# eMMC.net
KiCad netlist of a schematic drawn in Altium Designer
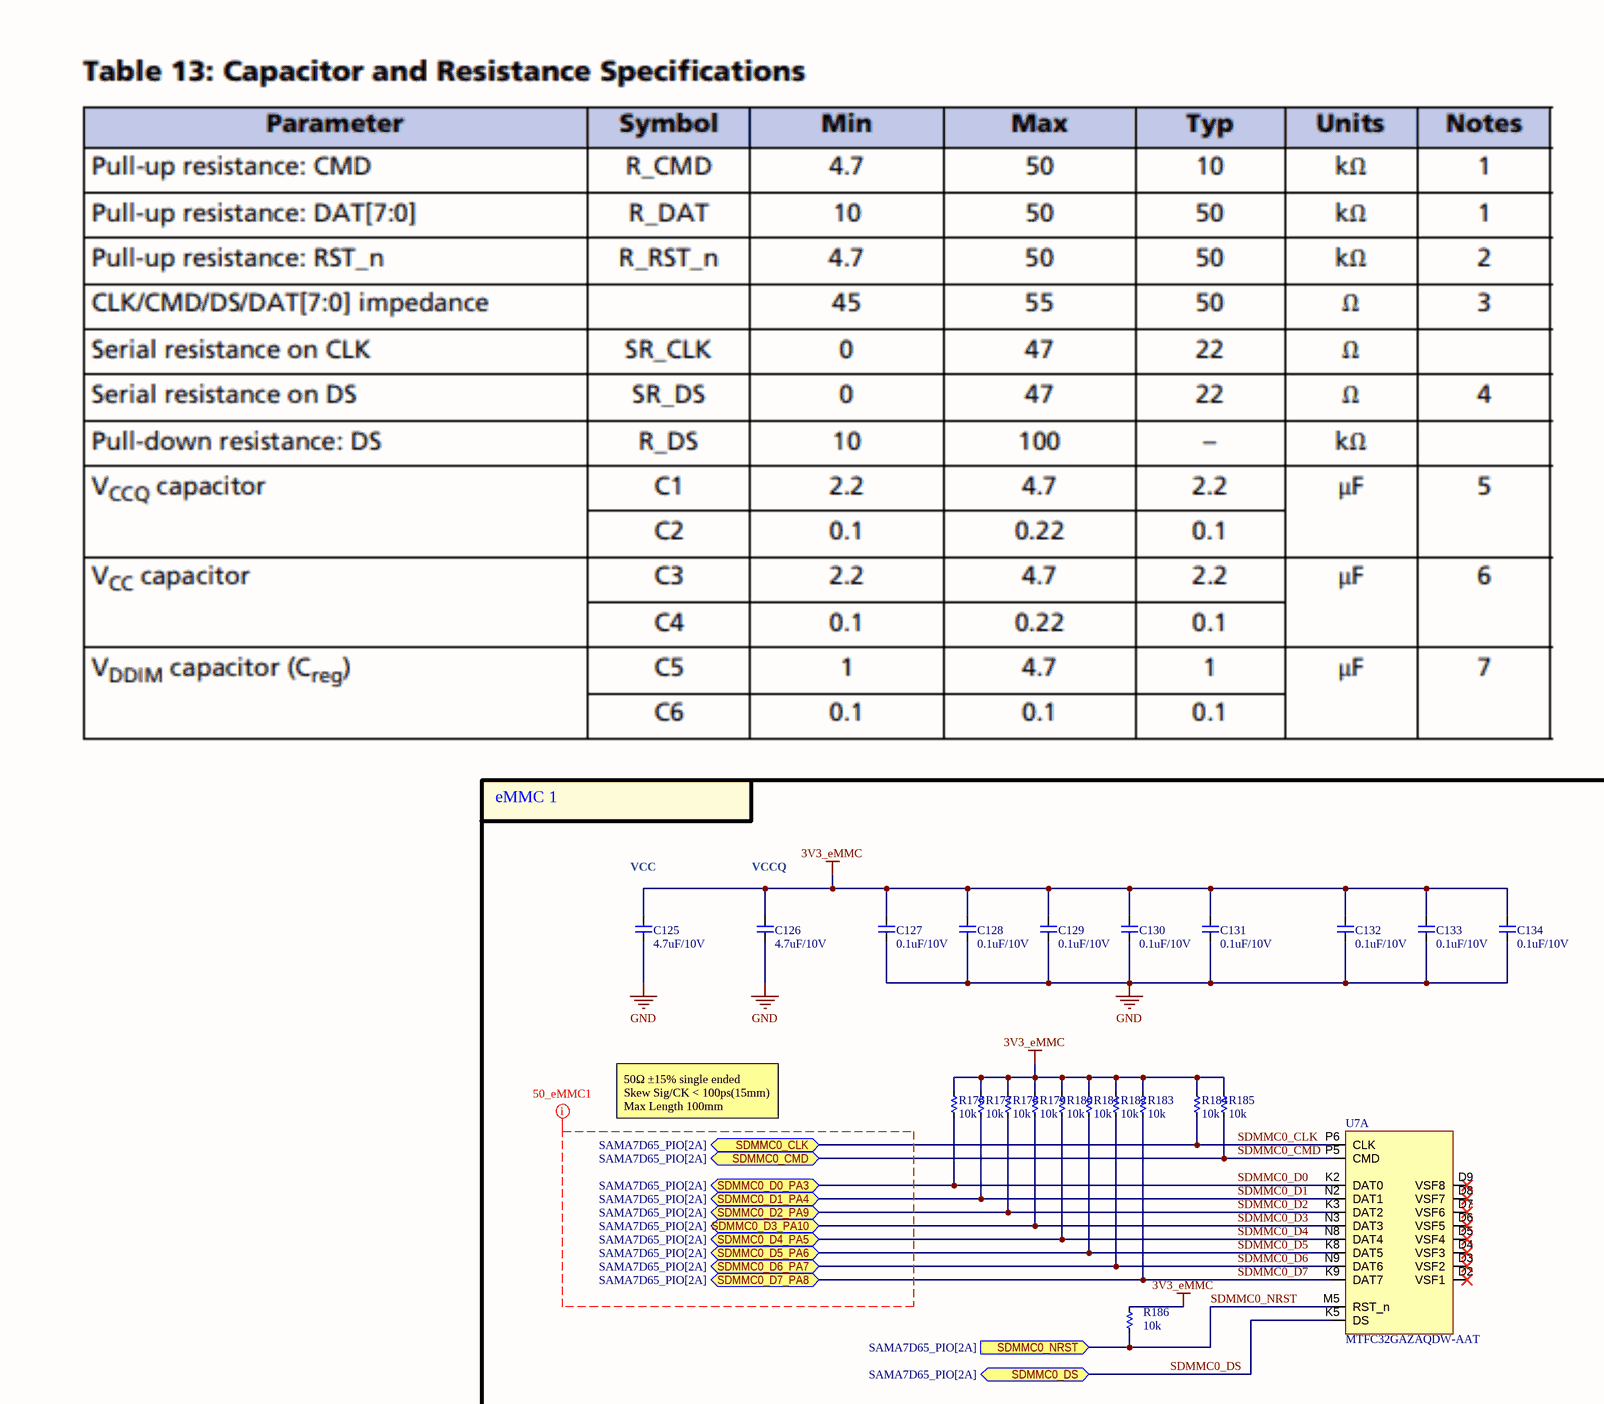
[diagram p0: eMMC.SchDoc, top left]
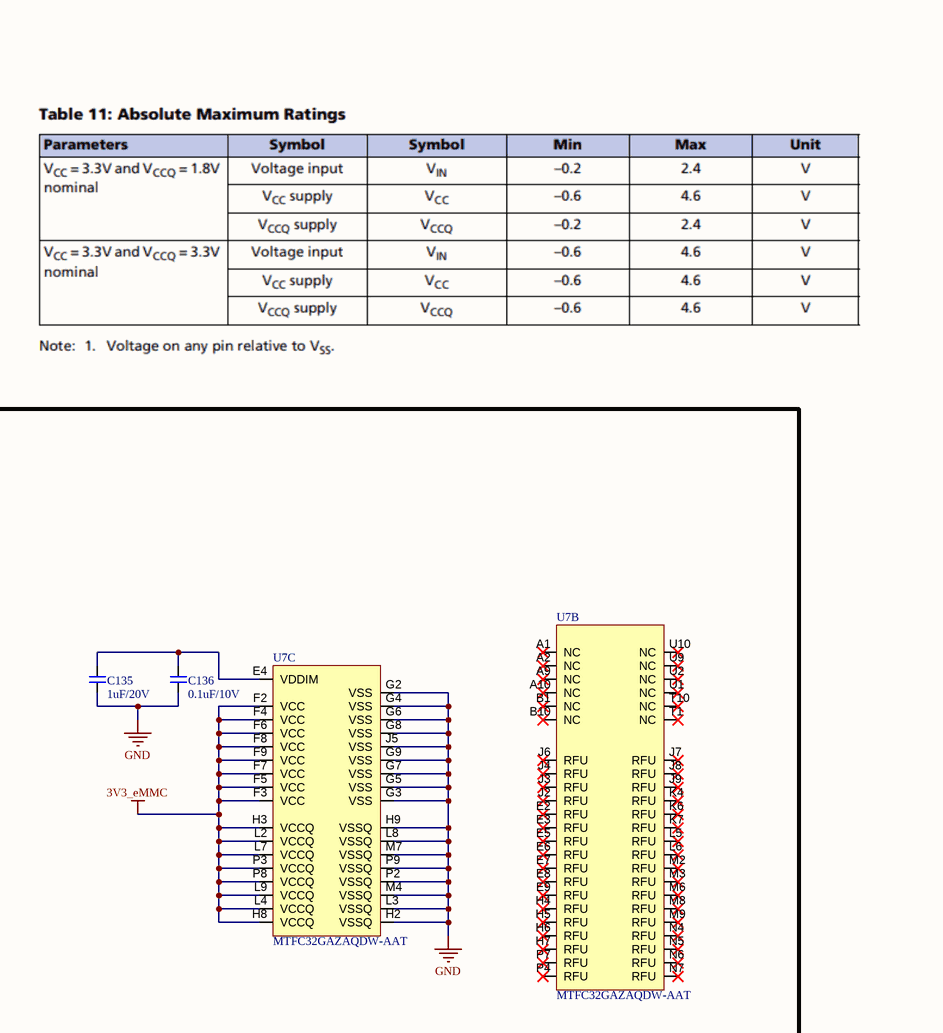
[diagram p1: eMMC.SchDoc, top middle]
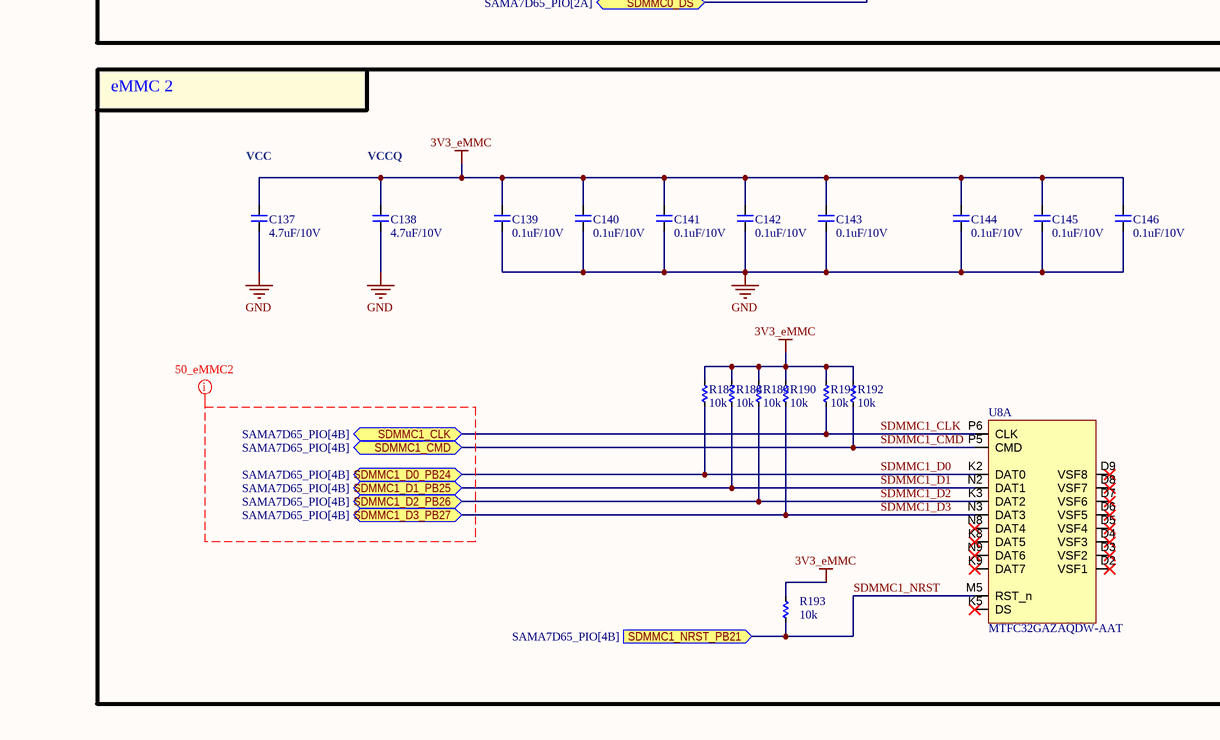
[diagram p2: eMMC.SchDoc, bottom left]
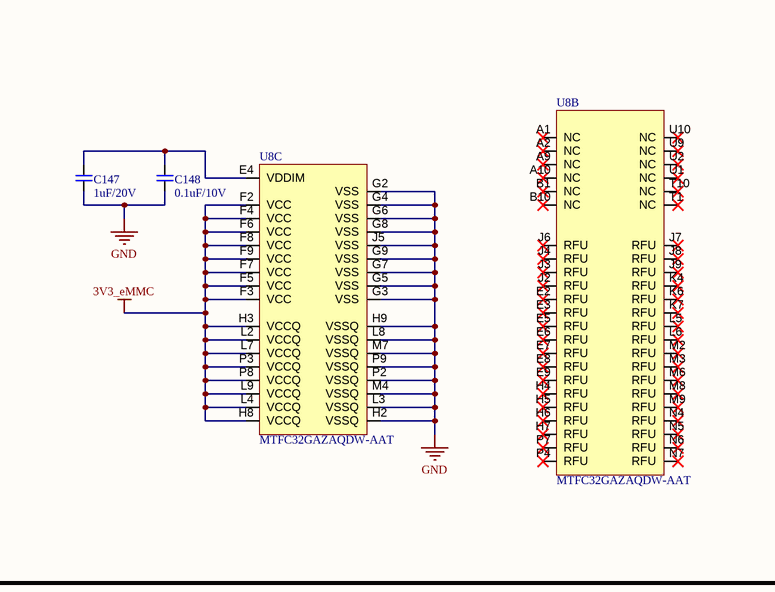
[diagram p3: eMMC.SchDoc, bottom middle]
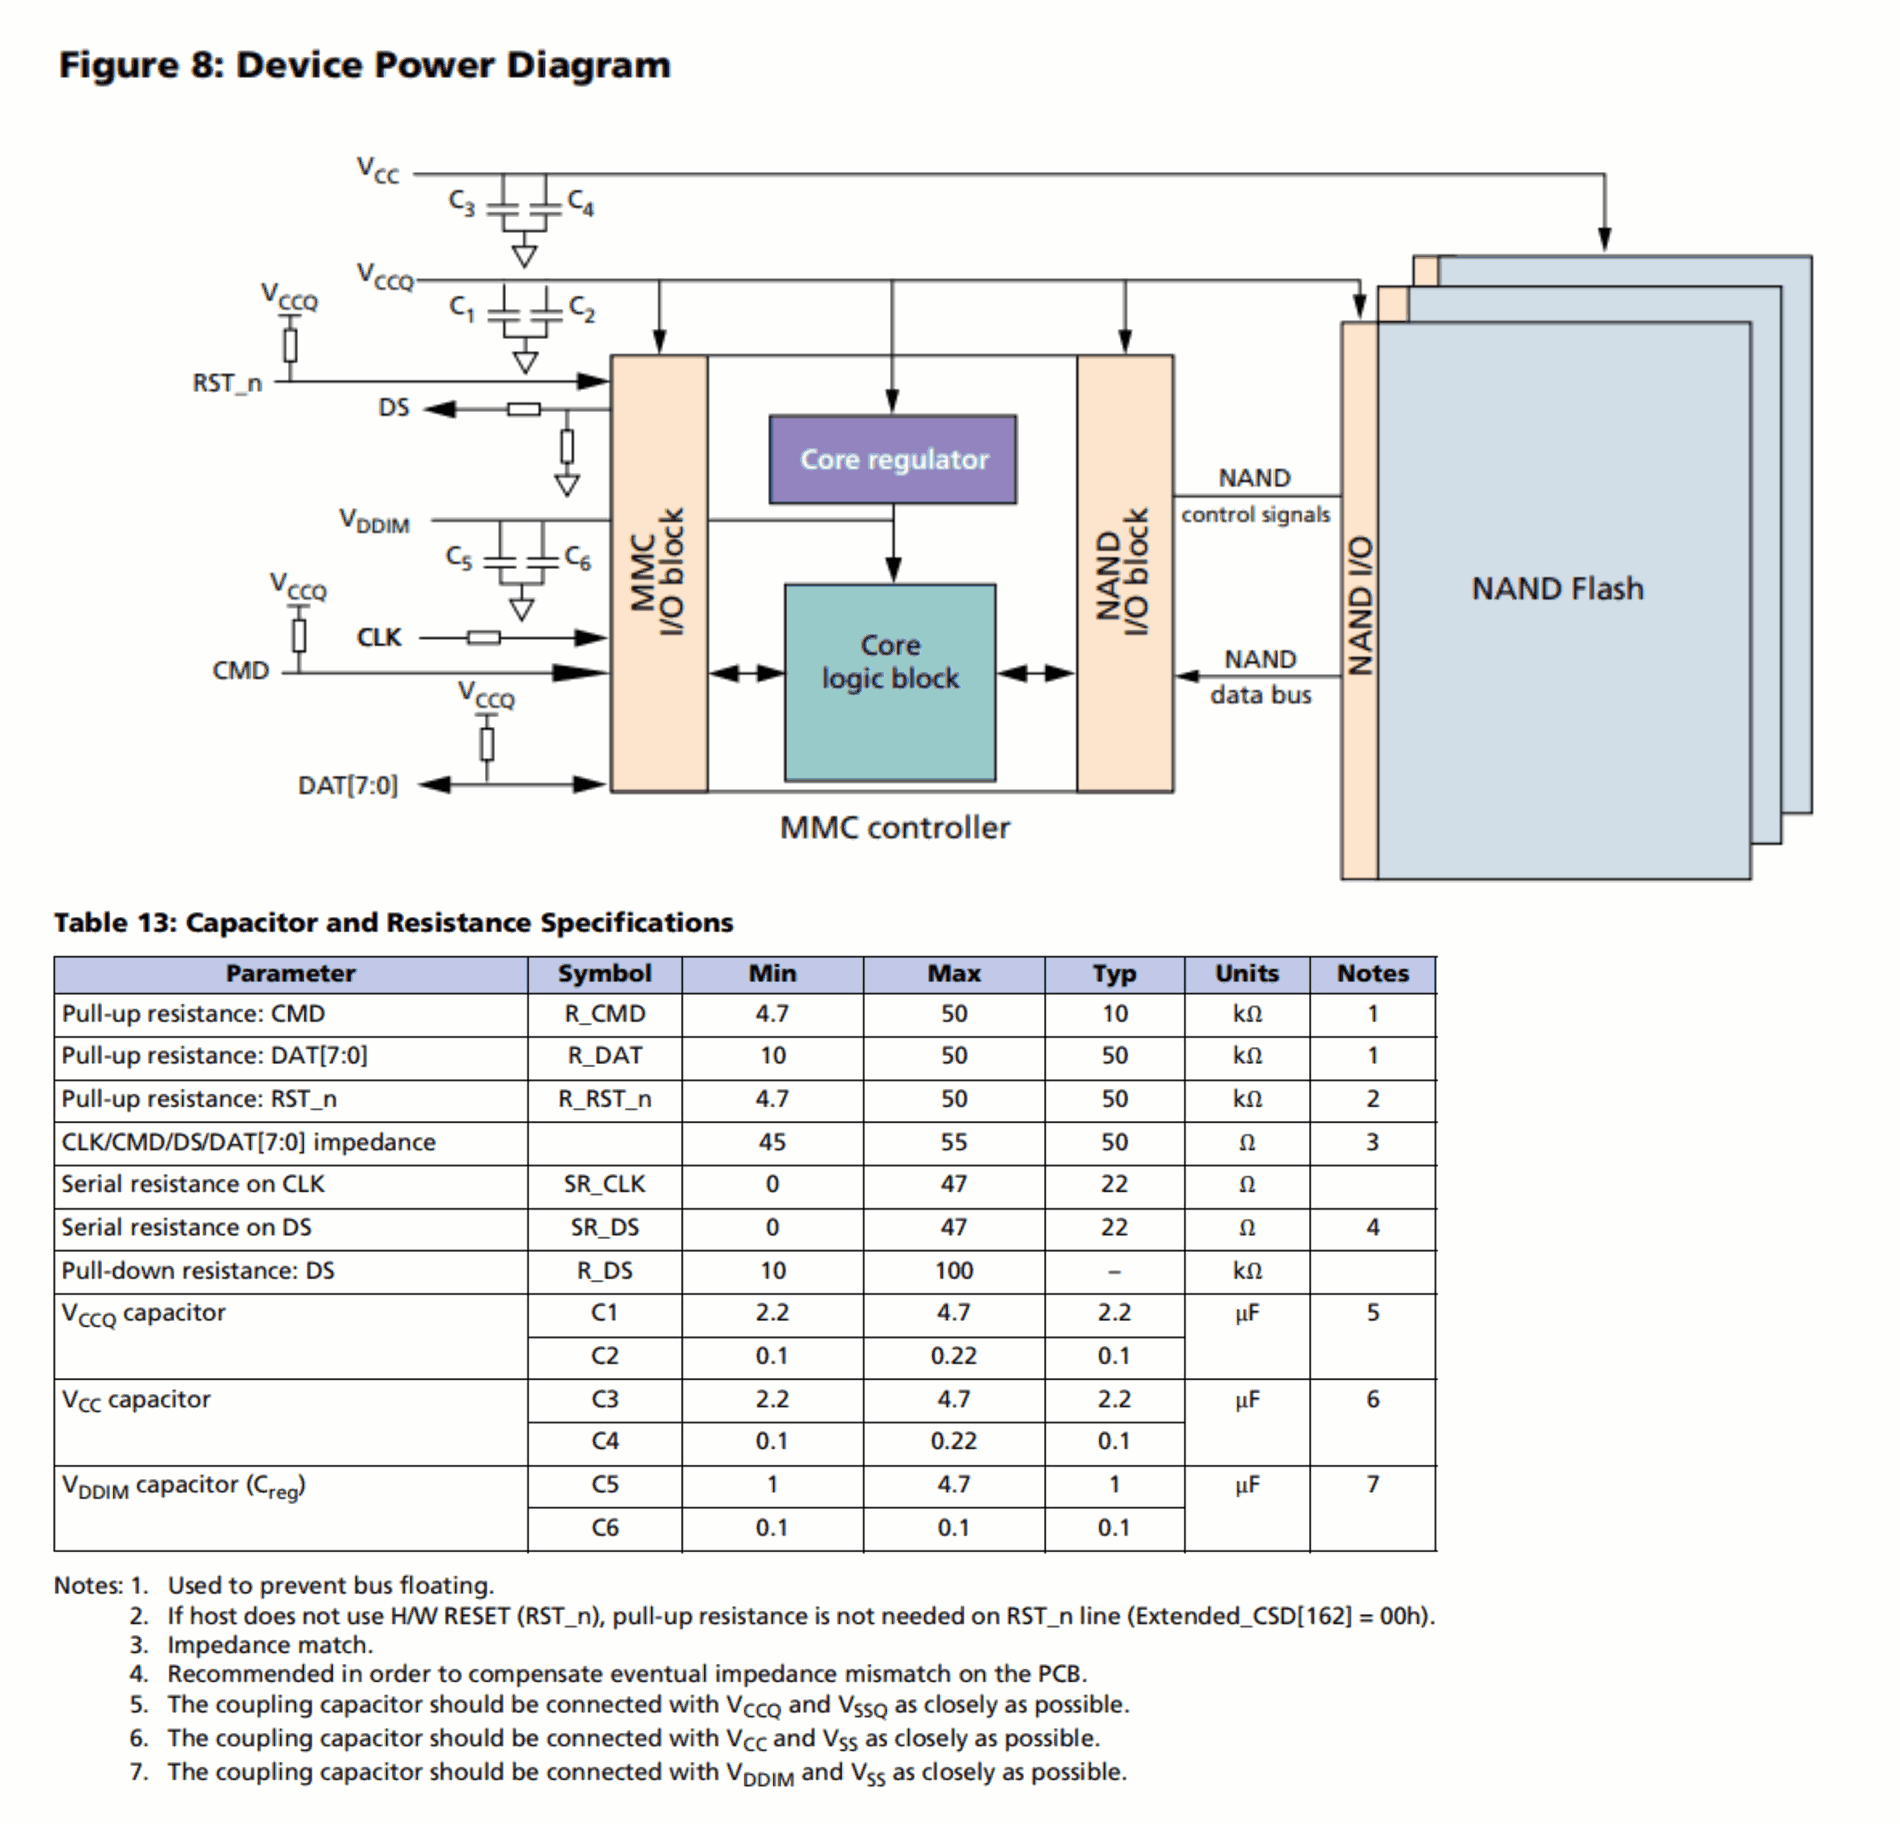
[diagram p4: eMMC.SchDoc, bottom right]

(export (version "E")
  (design (tool "Eeschema 10.0.6"))
  (components
    (comp (ref "C125")
      (value "4.7uF/10V")
      (footprint "CAP_C_1005X50_L")
      (description "CAP CHIP")
      (libsource (lib "IFBschelib") (part "_CAP_C_2"))
    )
    (comp (ref "C126")
      (value "4.7uF/10V")
      (footprint "CAP_C_1005X50_L")
      (description "CAP CHIP")
      (libsource (lib "IFBschelib") (part "_CAP_C_2"))
    )
    (comp (ref "C127")
      (value "0.1uF/10V")
      (footprint "CAP_C_1005X50_L")
      (description "CAP CHIP")
      (libsource (lib "IFBschelib") (part "_CAP_C_2"))
    )
    (comp (ref "C128")
      (value "0.1uF/10V")
      (footprint "CAP_C_1005X50_L")
      (description "CAP CHIP")
      (libsource (lib "IFBschelib") (part "_CAP_C_2"))
    )
    (comp (ref "C129")
      (value "0.1uF/10V")
      (footprint "CAP_C_1005X50_L")
      (description "CAP CHIP")
      (libsource (lib "IFBschelib") (part "_CAP_C_2"))
    )
    (comp (ref "C130")
      (value "0.1uF/10V")
      (footprint "CAP_C_1005X50_L")
      (description "CAP CHIP")
      (libsource (lib "IFBschelib") (part "_CAP_C_2"))
    )
    (comp (ref "C131")
      (value "0.1uF/10V")
      (footprint "CAP_C_1005X50_L")
      (description "CAP CHIP")
      (libsource (lib "IFBschelib") (part "_CAP_C_2"))
    )
    (comp (ref "C132")
      (value "0.1uF/10V")
      (footprint "CAP_C_1005X50_L")
      (description "CAP CHIP")
      (libsource (lib "IFBschelib") (part "_CAP_C_2"))
    )
    (comp (ref "C133")
      (value "0.1uF/10V")
      (footprint "CAP_C_1005X50_L")
      (description "CAP CHIP")
      (libsource (lib "IFBschelib") (part "_CAP_C_2"))
    )
    (comp (ref "C134")
      (value "0.1uF/10V")
      (footprint "CAP_C_1005X50_L")
      (description "CAP CHIP")
      (libsource (lib "IFBschelib") (part "_CAP_C_2"))
    )
    (comp (ref "C135")
      (value "1uF/20V")
      (footprint "CAP_C_1005X50_L")
      (description "CAP CHIP")
      (libsource (lib "IFBschelib") (part "_CAP_C_2"))
    )
    (comp (ref "C136")
      (value "0.1uF/10V")
      (footprint "CAP_C_1005X50_L")
      (description "CAP CHIP")
      (libsource (lib "IFBschelib") (part "_CAP_C_2"))
    )
    (comp (ref "C137")
      (value "4.7uF/10V")
      (footprint "CAP_C_1005X50_L")
      (description "CAP CHIP")
      (libsource (lib "IFBschelib") (part "_CAP_C_2"))
    )
    (comp (ref "C138")
      (value "4.7uF/10V")
      (footprint "CAP_C_1005X50_L")
      (description "CAP CHIP")
      (libsource (lib "IFBschelib") (part "_CAP_C_2"))
    )
    (comp (ref "C139")
      (value "0.1uF/10V")
      (footprint "CAP_C_1005X50_L")
      (description "CAP CHIP")
      (libsource (lib "IFBschelib") (part "_CAP_C_2"))
    )
    (comp (ref "C140")
      (value "0.1uF/10V")
      (footprint "CAP_C_1005X50_L")
      (description "CAP CHIP")
      (libsource (lib "IFBschelib") (part "_CAP_C_2"))
    )
    (comp (ref "C141")
      (value "0.1uF/10V")
      (footprint "CAP_C_1005X50_L")
      (description "CAP CHIP")
      (libsource (lib "IFBschelib") (part "_CAP_C_2"))
    )
    (comp (ref "C142")
      (value "0.1uF/10V")
      (footprint "CAP_C_1005X50_L")
      (description "CAP CHIP")
      (libsource (lib "IFBschelib") (part "_CAP_C_2"))
    )
    (comp (ref "C143")
      (value "0.1uF/10V")
      (footprint "CAP_C_1005X50_L")
      (description "CAP CHIP")
      (libsource (lib "IFBschelib") (part "_CAP_C_2"))
    )
    (comp (ref "C144")
      (value "0.1uF/10V")
      (footprint "CAP_C_1005X50_L")
      (description "CAP CHIP")
      (libsource (lib "IFBschelib") (part "_CAP_C_2"))
    )
    (comp (ref "C145")
      (value "0.1uF/10V")
      (footprint "CAP_C_1005X50_L")
      (description "CAP CHIP")
      (libsource (lib "IFBschelib") (part "_CAP_C_2"))
    )
    (comp (ref "C146")
      (value "0.1uF/10V")
      (footprint "CAP_C_1005X50_L")
      (description "CAP CHIP")
      (libsource (lib "IFBschelib") (part "_CAP_C_2"))
    )
    (comp (ref "C147")
      (value "1uF/20V")
      (footprint "CAP_C_1005X50_L")
      (description "CAP CHIP")
      (libsource (lib "IFBschelib") (part "_CAP_C_2"))
    )
    (comp (ref "C148")
      (value "0.1uF/10V")
      (footprint "CAP_C_1005X50_L")
      (description "CAP CHIP")
      (libsource (lib "IFBschelib") (part "_CAP_C_2"))
    )
    (comp (ref "R176")
      (value "10k")
      (footprint "RES_C_1005x30_L")
      (description "RES")
      (libsource (lib "IFBschelib") (part "_RES_B_2"))
    )
    (comp (ref "R177")
      (value "10k")
      (footprint "RES_C_1005x30_L")
      (description "RES")
      (libsource (lib "IFBschelib") (part "_RES_B_2"))
    )
    (comp (ref "R178")
      (value "10k")
      (footprint "RES_C_1005x30_L")
      (description "RES")
      (libsource (lib "IFBschelib") (part "_RES_B_2"))
    )
    (comp (ref "R179")
      (value "10k")
      (footprint "RES_C_1005x30_L")
      (description "RES")
      (libsource (lib "IFBschelib") (part "_RES_B_2"))
    )
    (comp (ref "R180")
      (value "10k")
      (footprint "RES_C_1005x30_L")
      (description "RES")
      (libsource (lib "IFBschelib") (part "_RES_B_2"))
    )
    (comp (ref "R181")
      (value "10k")
      (footprint "RES_C_1005x30_L")
      (description "RES")
      (libsource (lib "IFBschelib") (part "_RES_B_2"))
    )
    (comp (ref "R182")
      (value "10k")
      (footprint "RES_C_1005x30_L")
      (description "RES")
      (libsource (lib "IFBschelib") (part "_RES_B_2"))
    )
    (comp (ref "R183")
      (value "10k")
      (footprint "RES_C_1005x30_L")
      (description "RES")
      (libsource (lib "IFBschelib") (part "_RES_B_2"))
    )
    (comp (ref "R184")
      (value "10k")
      (footprint "RES_C_1005x30_L")
      (description "RES")
      (libsource (lib "IFBschelib") (part "_RES_B_2"))
    )
    (comp (ref "R185")
      (value "10k")
      (footprint "RES_C_1005x30_L")
      (description "RES")
      (libsource (lib "IFBschelib") (part "_RES_B_2"))
    )
    (comp (ref "R186")
      (value "10k")
      (footprint "RES_C_1005x30_L")
      (description "RES")
      (libsource (lib "IFBschelib") (part "_RES_B_2"))
    )
    (comp (ref "R187")
      (value "10k")
      (footprint "RES_C_1005x30_L")
      (description "RES")
      (libsource (lib "IFBschelib") (part "_RES_B_2"))
    )
    (comp (ref "R188")
      (value "10k")
      (footprint "RES_C_1005x30_L")
      (description "RES")
      (libsource (lib "IFBschelib") (part "_RES_B_2"))
    )
    (comp (ref "R189")
      (value "10k")
      (footprint "RES_C_1005x30_L")
      (description "RES")
      (libsource (lib "IFBschelib") (part "_RES_B_2"))
    )
    (comp (ref "R190")
      (value "10k")
      (footprint "RES_C_1005x30_L")
      (description "RES")
      (libsource (lib "IFBschelib") (part "_RES_B_2"))
    )
    (comp (ref "R191")
      (value "10k")
      (footprint "RES_C_1005x30_L")
      (description "RES")
      (libsource (lib "IFBschelib") (part "_RES_B_2"))
    )
    (comp (ref "R192")
      (value "10k")
      (footprint "RES_C_1005x30_L")
      (description "RES")
      (libsource (lib "IFBschelib") (part "_RES_B_2"))
    )
    (comp (ref "R193")
      (value "10k")
      (footprint "RES_C_1005x30_L")
      (description "RES")
      (libsource (lib "IFBschelib") (part "_RES_B_2"))
    )
    (comp (ref "U7")
      (value "MTFC32GAZAQDW-AAT")
      (footprint "BGA_100_C_100P_10X17_1400X1800X150")
      (libsource (lib "IFBschelib") (part "MTFC32GAZAQDW-AAT"))
    )
    (comp (ref "U8")
      (value "MTFC32GAZAQDW-AAT")
      (footprint "BGA_100_C_100P_10X17_1400X1800X150")
      (libsource (lib "IFBschelib") (part "MTFC32GAZAQDW-AAT"))
    )
  )
  (nets
    (net (code "1") (name "/SDMMC0_CLK") (class "Default")
      (node (ref "R184") (pin "2") (pinfunction "2_2") (pintype "passive"))
      (node (ref "U7") (pin "P6") (pinfunction "CLK_P6") (pintype "passive"))
    )
    (net (code "2") (name "/SDMMC0_CMD") (class "Default")
      (node (ref "R185") (pin "2") (pinfunction "2_2") (pintype "passive"))
      (node (ref "U7") (pin "P5") (pinfunction "CMD_P5") (pintype "passive"))
    )
    (net (code "3") (name "/SDMMC0_D0") (class "Default")
      (node (ref "R176") (pin "2") (pinfunction "2_2") (pintype "passive"))
      (node (ref "U7") (pin "K2") (pinfunction "DAT0_K2") (pintype "passive"))
    )
    (net (code "4") (name "/SDMMC0_D1") (class "Default")
      (node (ref "R177") (pin "2") (pinfunction "2_2") (pintype "passive"))
      (node (ref "U7") (pin "N2") (pinfunction "DAT1_N2") (pintype "passive"))
    )
    (net (code "5") (name "/SDMMC0_D2") (class "Default")
      (node (ref "R178") (pin "2") (pinfunction "2_2") (pintype "passive"))
      (node (ref "U7") (pin "K3") (pinfunction "DAT2_K3") (pintype "passive"))
    )
    (net (code "6") (name "/SDMMC0_D3") (class "Default")
      (node (ref "R179") (pin "2") (pinfunction "2_2") (pintype "passive"))
      (node (ref "U7") (pin "N3") (pinfunction "DAT3_N3") (pintype "passive"))
    )
    (net (code "7") (name "/SDMMC0_D4") (class "Default")
      (node (ref "R180") (pin "2") (pinfunction "2_2") (pintype "passive"))
      (node (ref "U7") (pin "N8") (pinfunction "DAT4_N8") (pintype "passive"))
    )
    (net (code "8") (name "/SDMMC0_D5") (class "Default")
      (node (ref "R181") (pin "2") (pinfunction "2_2") (pintype "passive"))
      (node (ref "U7") (pin "K8") (pinfunction "DAT5_K8") (pintype "passive"))
    )
    (net (code "9") (name "/SDMMC0_D6") (class "Default")
      (node (ref "R182") (pin "2") (pinfunction "2_2") (pintype "passive"))
      (node (ref "U7") (pin "N9") (pinfunction "DAT6_N9") (pintype "passive"))
    )
    (net (code "10") (name "/SDMMC0_D7") (class "Default")
      (node (ref "R183") (pin "2") (pinfunction "2_2") (pintype "passive"))
      (node (ref "U7") (pin "K9") (pinfunction "DAT7_K9") (pintype "passive"))
    )
    (net (code "11") (name "/SDMMC0_DS") (class "Default")
      (node (ref "U7") (pin "K5") (pinfunction "DS_K5") (pintype "passive"))
    )
    (net (code "12") (name "/SDMMC0_NRST") (class "Default")
      (node (ref "R186") (pin "2") (pinfunction "2_2") (pintype "passive"))
      (node (ref "U7") (pin "M5") (pinfunction "RST_n_M5") (pintype "passive"))
    )
    (net (code "13") (name "/SDMMC1_CLK") (class "Default")
      (node (ref "R191") (pin "2") (pinfunction "2_2") (pintype "passive"))
      (node (ref "U8") (pin "P6") (pinfunction "CLK_P6") (pintype "passive"))
    )
    (net (code "14") (name "/SDMMC1_CMD") (class "Default")
      (node (ref "R192") (pin "2") (pinfunction "2_2") (pintype "passive"))
      (node (ref "U8") (pin "P5") (pinfunction "CMD_P5") (pintype "passive"))
    )
    (net (code "15") (name "/SDMMC1_D0") (class "Default")
      (node (ref "R187") (pin "2") (pinfunction "2_2") (pintype "passive"))
      (node (ref "U8") (pin "K2") (pinfunction "DAT0_K2") (pintype "passive"))
    )
    (net (code "16") (name "/SDMMC1_D1") (class "Default")
      (node (ref "R188") (pin "2") (pinfunction "2_2") (pintype "passive"))
      (node (ref "U8") (pin "N2") (pinfunction "DAT1_N2") (pintype "passive"))
    )
    (net (code "17") (name "/SDMMC1_D2") (class "Default")
      (node (ref "R189") (pin "2") (pinfunction "2_2") (pintype "passive"))
      (node (ref "U8") (pin "K3") (pinfunction "DAT2_K3") (pintype "passive"))
    )
    (net (code "18") (name "/SDMMC1_D3") (class "Default")
      (node (ref "R190") (pin "2") (pinfunction "2_2") (pintype "passive"))
      (node (ref "U8") (pin "N3") (pinfunction "DAT3_N3") (pintype "passive"))
    )
    (net (code "19") (name "/SDMMC1_NRST") (class "Default")
      (node (ref "R193") (pin "2") (pinfunction "2_2") (pintype "passive"))
      (node (ref "U8") (pin "M5") (pinfunction "RST_n_M5") (pintype "passive"))
    )
    (net (code "20") (name "3V3_eMMC") (class "Default")
      (node (ref "C125") (pin "2") (pinfunction "2_2") (pintype "passive"))
      (node (ref "C126") (pin "2") (pinfunction "2_2") (pintype "passive"))
      (node (ref "C127") (pin "2") (pinfunction "2_2") (pintype "passive"))
      (node (ref "C128") (pin "2") (pinfunction "2_2") (pintype "passive"))
      (node (ref "C129") (pin "2") (pinfunction "2_2") (pintype "passive"))
      (node (ref "C130") (pin "2") (pinfunction "2_2") (pintype "passive"))
      (node (ref "C131") (pin "2") (pinfunction "2_2") (pintype "passive"))
      (node (ref "C132") (pin "2") (pinfunction "2_2") (pintype "passive"))
      (node (ref "C133") (pin "2") (pinfunction "2_2") (pintype "passive"))
      (node (ref "C134") (pin "2") (pinfunction "2_2") (pintype "passive"))
      (node (ref "C137") (pin "2") (pinfunction "2_2") (pintype "passive"))
      (node (ref "C138") (pin "2") (pinfunction "2_2") (pintype "passive"))
      (node (ref "C139") (pin "2") (pinfunction "2_2") (pintype "passive"))
      (node (ref "C140") (pin "2") (pinfunction "2_2") (pintype "passive"))
      (node (ref "C141") (pin "2") (pinfunction "2_2") (pintype "passive"))
      (node (ref "C142") (pin "2") (pinfunction "2_2") (pintype "passive"))
      (node (ref "C143") (pin "2") (pinfunction "2_2") (pintype "passive"))
      (node (ref "C144") (pin "2") (pinfunction "2_2") (pintype "passive"))
      (node (ref "C145") (pin "2") (pinfunction "2_2") (pintype "passive"))
      (node (ref "C146") (pin "2") (pinfunction "2_2") (pintype "passive"))
      (node (ref "R176") (pin "1") (pinfunction "1_1") (pintype "passive"))
      (node (ref "R177") (pin "1") (pinfunction "1_1") (pintype "passive"))
      (node (ref "R178") (pin "1") (pinfunction "1_1") (pintype "passive"))
      (node (ref "R179") (pin "1") (pinfunction "1_1") (pintype "passive"))
      (node (ref "R180") (pin "1") (pinfunction "1_1") (pintype "passive"))
      (node (ref "R181") (pin "1") (pinfunction "1_1") (pintype "passive"))
      (node (ref "R182") (pin "1") (pinfunction "1_1") (pintype "passive"))
      (node (ref "R183") (pin "1") (pinfunction "1_1") (pintype "passive"))
      (node (ref "R184") (pin "1") (pinfunction "1_1") (pintype "passive"))
      (node (ref "R185") (pin "1") (pinfunction "1_1") (pintype "passive"))
      (node (ref "R186") (pin "1") (pinfunction "1_1") (pintype "passive"))
      (node (ref "R187") (pin "1") (pinfunction "1_1") (pintype "passive"))
      (node (ref "R188") (pin "1") (pinfunction "1_1") (pintype "passive"))
      (node (ref "R189") (pin "1") (pinfunction "1_1") (pintype "passive"))
      (node (ref "R190") (pin "1") (pinfunction "1_1") (pintype "passive"))
      (node (ref "R191") (pin "1") (pinfunction "1_1") (pintype "passive"))
      (node (ref "R192") (pin "1") (pinfunction "1_1") (pintype "passive"))
      (node (ref "R193") (pin "1") (pinfunction "1_1") (pintype "passive"))
      (node (ref "U7") (pin "F2") (pinfunction "VCC_F2") (pintype "passive"))
      (node (ref "U7") (pin "F3") (pinfunction "VCC_F3") (pintype "passive"))
      (node (ref "U7") (pin "F4") (pinfunction "VCC_F4") (pintype "passive"))
      (node (ref "U7") (pin "F5") (pinfunction "VCC_F5") (pintype "passive"))
      (node (ref "U7") (pin "F6") (pinfunction "VCC_F6") (pintype "passive"))
      (node (ref "U7") (pin "F7") (pinfunction "VCC_F7") (pintype "passive"))
      (node (ref "U7") (pin "F8") (pinfunction "VCC_F8") (pintype "passive"))
      (node (ref "U7") (pin "F9") (pinfunction "VCC_F9") (pintype "passive"))
      (node (ref "U7") (pin "H3") (pinfunction "VCCQ_H3") (pintype "passive"))
      (node (ref "U7") (pin "H8") (pinfunction "VCCQ_H8") (pintype "passive"))
      (node (ref "U7") (pin "L2") (pinfunction "VCCQ_L2") (pintype "passive"))
      (node (ref "U7") (pin "L4") (pinfunction "VCCQ_L4") (pintype "passive"))
      (node (ref "U7") (pin "L7") (pinfunction "VCCQ_L7") (pintype "passive"))
      (node (ref "U7") (pin "L9") (pinfunction "VCCQ_L9") (pintype "passive"))
      (node (ref "U7") (pin "P3") (pinfunction "VCCQ_P3") (pintype "passive"))
      (node (ref "U7") (pin "P8") (pinfunction "VCCQ_P8") (pintype "passive"))
      (node (ref "U8") (pin "F2") (pinfunction "VCC_F2") (pintype "passive"))
      (node (ref "U8") (pin "F3") (pinfunction "VCC_F3") (pintype "passive"))
      (node (ref "U8") (pin "F4") (pinfunction "VCC_F4") (pintype "passive"))
      (node (ref "U8") (pin "F5") (pinfunction "VCC_F5") (pintype "passive"))
      (node (ref "U8") (pin "F6") (pinfunction "VCC_F6") (pintype "passive"))
      (node (ref "U8") (pin "F7") (pinfunction "VCC_F7") (pintype "passive"))
      (node (ref "U8") (pin "F8") (pinfunction "VCC_F8") (pintype "passive"))
      (node (ref "U8") (pin "F9") (pinfunction "VCC_F9") (pintype "passive"))
      (node (ref "U8") (pin "H3") (pinfunction "VCCQ_H3") (pintype "passive"))
      (node (ref "U8") (pin "H8") (pinfunction "VCCQ_H8") (pintype "passive"))
      (node (ref "U8") (pin "L2") (pinfunction "VCCQ_L2") (pintype "passive"))
      (node (ref "U8") (pin "L4") (pinfunction "VCCQ_L4") (pintype "passive"))
      (node (ref "U8") (pin "L7") (pinfunction "VCCQ_L7") (pintype "passive"))
      (node (ref "U8") (pin "L9") (pinfunction "VCCQ_L9") (pintype "passive"))
      (node (ref "U8") (pin "P3") (pinfunction "VCCQ_P3") (pintype "passive"))
      (node (ref "U8") (pin "P8") (pinfunction "VCCQ_P8") (pintype "passive"))
    )
    (net (code "21") (name "GND") (class "Default")
      (node (ref "C125") (pin "1") (pinfunction "1_1") (pintype "passive"))
      (node (ref "C126") (pin "1") (pinfunction "1_1") (pintype "passive"))
      (node (ref "C127") (pin "1") (pinfunction "1_1") (pintype "passive"))
      (node (ref "C128") (pin "1") (pinfunction "1_1") (pintype "passive"))
      (node (ref "C129") (pin "1") (pinfunction "1_1") (pintype "passive"))
      (node (ref "C130") (pin "1") (pinfunction "1_1") (pintype "passive"))
      (node (ref "C131") (pin "1") (pinfunction "1_1") (pintype "passive"))
      (node (ref "C132") (pin "1") (pinfunction "1_1") (pintype "passive"))
      (node (ref "C133") (pin "1") (pinfunction "1_1") (pintype "passive"))
      (node (ref "C134") (pin "1") (pinfunction "1_1") (pintype "passive"))
      (node (ref "C135") (pin "1") (pinfunction "1_1") (pintype "passive"))
      (node (ref "C136") (pin "1") (pinfunction "1_1") (pintype "passive"))
      (node (ref "C137") (pin "1") (pinfunction "1_1") (pintype "passive"))
      (node (ref "C138") (pin "1") (pinfunction "1_1") (pintype "passive"))
      (node (ref "C139") (pin "1") (pinfunction "1_1") (pintype "passive"))
      (node (ref "C140") (pin "1") (pinfunction "1_1") (pintype "passive"))
      (node (ref "C141") (pin "1") (pinfunction "1_1") (pintype "passive"))
      (node (ref "C142") (pin "1") (pinfunction "1_1") (pintype "passive"))
      (node (ref "C143") (pin "1") (pinfunction "1_1") (pintype "passive"))
      (node (ref "C144") (pin "1") (pinfunction "1_1") (pintype "passive"))
      (node (ref "C145") (pin "1") (pinfunction "1_1") (pintype "passive"))
      (node (ref "C146") (pin "1") (pinfunction "1_1") (pintype "passive"))
      (node (ref "C147") (pin "1") (pinfunction "1_1") (pintype "passive"))
      (node (ref "C148") (pin "1") (pinfunction "1_1") (pintype "passive"))
      (node (ref "U7") (pin "G2") (pinfunction "VSS_G2") (pintype "passive"))
      (node (ref "U7") (pin "G3") (pinfunction "VSS_G3") (pintype "passive"))
      (node (ref "U7") (pin "G4") (pinfunction "VSS_G4") (pintype "passive"))
      (node (ref "U7") (pin "G5") (pinfunction "VSS_G5") (pintype "passive"))
      (node (ref "U7") (pin "G6") (pinfunction "VSS_G6") (pintype "passive"))
      (node (ref "U7") (pin "G7") (pinfunction "VSS_G7") (pintype "passive"))
      (node (ref "U7") (pin "G8") (pinfunction "VSS_G8") (pintype "passive"))
      (node (ref "U7") (pin "G9") (pinfunction "VSS_G9") (pintype "passive"))
      (node (ref "U7") (pin "H2") (pinfunction "VSSQ_H2") (pintype "passive"))
      (node (ref "U7") (pin "H9") (pinfunction "VSSQ_H9") (pintype "passive"))
      (node (ref "U7") (pin "J5") (pinfunction "VSS_J5") (pintype "passive"))
      (node (ref "U7") (pin "L3") (pinfunction "VSSQ_L3") (pintype "passive"))
      (node (ref "U7") (pin "L8") (pinfunction "VSSQ_L8") (pintype "passive"))
      (node (ref "U7") (pin "M4") (pinfunction "VSSQ_M4") (pintype "passive"))
      (node (ref "U7") (pin "M7") (pinfunction "VSSQ_M7") (pintype "passive"))
      (node (ref "U7") (pin "P2") (pinfunction "VSSQ_P2") (pintype "passive"))
      (node (ref "U7") (pin "P9") (pinfunction "VSSQ_P9") (pintype "passive"))
      (node (ref "U8") (pin "G2") (pinfunction "VSS_G2") (pintype "passive"))
      (node (ref "U8") (pin "G3") (pinfunction "VSS_G3") (pintype "passive"))
      (node (ref "U8") (pin "G4") (pinfunction "VSS_G4") (pintype "passive"))
      (node (ref "U8") (pin "G5") (pinfunction "VSS_G5") (pintype "passive"))
      (node (ref "U8") (pin "G6") (pinfunction "VSS_G6") (pintype "passive"))
      (node (ref "U8") (pin "G7") (pinfunction "VSS_G7") (pintype "passive"))
      (node (ref "U8") (pin "G8") (pinfunction "VSS_G8") (pintype "passive"))
      (node (ref "U8") (pin "G9") (pinfunction "VSS_G9") (pintype "passive"))
      (node (ref "U8") (pin "H2") (pinfunction "VSSQ_H2") (pintype "passive"))
      (node (ref "U8") (pin "H9") (pinfunction "VSSQ_H9") (pintype "passive"))
      (node (ref "U8") (pin "J5") (pinfunction "VSS_J5") (pintype "passive"))
      (node (ref "U8") (pin "L3") (pinfunction "VSSQ_L3") (pintype "passive"))
      (node (ref "U8") (pin "L8") (pinfunction "VSSQ_L8") (pintype "passive"))
      (node (ref "U8") (pin "M4") (pinfunction "VSSQ_M4") (pintype "passive"))
      (node (ref "U8") (pin "M7") (pinfunction "VSSQ_M7") (pintype "passive"))
      (node (ref "U8") (pin "P2") (pinfunction "VSSQ_P2") (pintype "passive"))
      (node (ref "U8") (pin "P9") (pinfunction "VSSQ_P9") (pintype "passive"))
    )
    (net (code "22") (name "Net-(U7C-VDDIM)") (class "Default")
      (node (ref "C135") (pin "2") (pinfunction "2_2") (pintype "passive"))
      (node (ref "C136") (pin "2") (pinfunction "2_2") (pintype "passive"))
      (node (ref "U7") (pin "E4") (pinfunction "VDDIM_E4") (pintype "passive"))
    )
    (net (code "23") (name "Net-(U8C-VDDIM)") (class "Default")
      (node (ref "C147") (pin "2") (pinfunction "2_2") (pintype "passive"))
      (node (ref "C148") (pin "2") (pinfunction "2_2") (pintype "passive"))
      (node (ref "U8") (pin "E4") (pinfunction "VDDIM_E4") (pintype "passive"))
    )
    (net (code "24") (name "unconnected-(U7A-VSF1-PadD2)") (class "Default")
      (node (ref "U7") (pin "D2") (pinfunction "VSF1_D2") (pintype "passive+no_connect"))
    )
    (net (code "25") (name "unconnected-(U7A-VSF2-PadD3)") (class "Default")
      (node (ref "U7") (pin "D3") (pinfunction "VSF2_D3") (pintype "passive+no_connect"))
    )
    (net (code "26") (name "unconnected-(U7A-VSF3-PadD4)") (class "Default")
      (node (ref "U7") (pin "D4") (pinfunction "VSF3_D4") (pintype "passive+no_connect"))
    )
    (net (code "27") (name "unconnected-(U7A-VSF4-PadD5)") (class "Default")
      (node (ref "U7") (pin "D5") (pinfunction "VSF4_D5") (pintype "passive+no_connect"))
    )
    (net (code "28") (name "unconnected-(U7A-VSF5-PadD6)") (class "Default")
      (node (ref "U7") (pin "D6") (pinfunction "VSF5_D6") (pintype "passive+no_connect"))
    )
    (net (code "29") (name "unconnected-(U7A-VSF6-PadD7)") (class "Default")
      (node (ref "U7") (pin "D7") (pinfunction "VSF6_D7") (pintype "passive+no_connect"))
    )
    (net (code "30") (name "unconnected-(U7A-VSF7-PadD8)") (class "Default")
      (node (ref "U7") (pin "D8") (pinfunction "VSF7_D8") (pintype "passive+no_connect"))
    )
    (net (code "31") (name "unconnected-(U7A-VSF8-PadD9)") (class "Default")
      (node (ref "U7") (pin "D9") (pinfunction "VSF8_D9") (pintype "passive+no_connect"))
    )
    (net (code "32") (name "unconnected-(U7B-NC-PadA1)") (class "Default")
      (node (ref "U7") (pin "A1") (pinfunction "NC_A1") (pintype "passive+no_connect"))
    )
    (net (code "33") (name "unconnected-(U7B-NC-PadA2)") (class "Default")
      (node (ref "U7") (pin "A2") (pinfunction "NC_A2") (pintype "passive+no_connect"))
    )
    (net (code "34") (name "unconnected-(U7B-NC-PadA9)") (class "Default")
      (node (ref "U7") (pin "A9") (pinfunction "NC_A9") (pintype "passive+no_connect"))
    )
    (net (code "35") (name "unconnected-(U7B-NC-PadA10)") (class "Default")
      (node (ref "U7") (pin "A10") (pinfunction "NC_A10") (pintype "passive+no_connect"))
    )
    (net (code "36") (name "unconnected-(U7B-NC-PadB1)") (class "Default")
      (node (ref "U7") (pin "B1") (pinfunction "NC_B1") (pintype "passive+no_connect"))
    )
    (net (code "37") (name "unconnected-(U7B-NC-PadB10)") (class "Default")
      (node (ref "U7") (pin "B10") (pinfunction "NC_B10") (pintype "passive+no_connect"))
    )
    (net (code "38") (name "unconnected-(U7B-NC-PadT1)") (class "Default")
      (node (ref "U7") (pin "T1") (pinfunction "NC_T1") (pintype "passive+no_connect"))
    )
    (net (code "39") (name "unconnected-(U7B-NC-PadT10)") (class "Default")
      (node (ref "U7") (pin "T10") (pinfunction "NC_T10") (pintype "passive+no_connect"))
    )
    (net (code "40") (name "unconnected-(U7B-NC-PadU1)") (class "Default")
      (node (ref "U7") (pin "U1") (pinfunction "NC_U1") (pintype "passive+no_connect"))
    )
    (net (code "41") (name "unconnected-(U7B-NC-PadU2)") (class "Default")
      (node (ref "U7") (pin "U2") (pinfunction "NC_U2") (pintype "passive+no_connect"))
    )
    (net (code "42") (name "unconnected-(U7B-NC-PadU9)") (class "Default")
      (node (ref "U7") (pin "U9") (pinfunction "NC_U9") (pintype "passive+no_connect"))
    )
    (net (code "43") (name "unconnected-(U7B-NC-PadU10)") (class "Default")
      (node (ref "U7") (pin "U10") (pinfunction "NC_U10") (pintype "passive+no_connect"))
    )
    (net (code "44") (name "unconnected-(U7B-RFU-PadE2)") (class "Default")
      (node (ref "U7") (pin "E2") (pinfunction "RFU_E2") (pintype "passive+no_connect"))
    )
    (net (code "45") (name "unconnected-(U7B-RFU-PadE3)") (class "Default")
      (node (ref "U7") (pin "E3") (pinfunction "RFU_E3") (pintype "passive+no_connect"))
    )
    (net (code "46") (name "unconnected-(U7B-RFU-PadE5)") (class "Default")
      (node (ref "U7") (pin "E5") (pinfunction "RFU_E5") (pintype "passive+no_connect"))
    )
    (net (code "47") (name "unconnected-(U7B-RFU-PadE6)") (class "Default")
      (node (ref "U7") (pin "E6") (pinfunction "RFU_E6") (pintype "passive+no_connect"))
    )
    (net (code "48") (name "unconnected-(U7B-RFU-PadE7)") (class "Default")
      (node (ref "U7") (pin "E7") (pinfunction "RFU_E7") (pintype "passive+no_connect"))
    )
    (net (code "49") (name "unconnected-(U7B-RFU-PadE8)") (class "Default")
      (node (ref "U7") (pin "E8") (pinfunction "RFU_E8") (pintype "passive+no_connect"))
    )
    (net (code "50") (name "unconnected-(U7B-RFU-PadE9)") (class "Default")
      (node (ref "U7") (pin "E9") (pinfunction "RFU_E9") (pintype "passive+no_connect"))
    )
    (net (code "51") (name "unconnected-(U7B-RFU-PadH4)") (class "Default")
      (node (ref "U7") (pin "H4") (pinfunction "RFU_H4") (pintype "passive+no_connect"))
    )
    (net (code "52") (name "unconnected-(U7B-RFU-PadH5)") (class "Default")
      (node (ref "U7") (pin "H5") (pinfunction "RFU_H5") (pintype "passive+no_connect"))
    )
    (net (code "53") (name "unconnected-(U7B-RFU-PadH6)") (class "Default")
      (node (ref "U7") (pin "H6") (pinfunction "RFU_H6") (pintype "passive+no_connect"))
    )
    (net (code "54") (name "unconnected-(U7B-RFU-PadH7)") (class "Default")
      (node (ref "U7") (pin "H7") (pinfunction "RFU_H7") (pintype "passive+no_connect"))
    )
    (net (code "55") (name "unconnected-(U7B-RFU-PadJ2)") (class "Default")
      (node (ref "U7") (pin "J2") (pinfunction "RFU_J2") (pintype "passive+no_connect"))
    )
    (net (code "56") (name "unconnected-(U7B-RFU-PadJ3)") (class "Default")
      (node (ref "U7") (pin "J3") (pinfunction "RFU_J3") (pintype "passive+no_connect"))
    )
    (net (code "57") (name "unconnected-(U7B-RFU-PadJ4)") (class "Default")
      (node (ref "U7") (pin "J4") (pinfunction "RFU_J4") (pintype "passive+no_connect"))
    )
    (net (code "58") (name "unconnected-(U7B-RFU-PadJ6)") (class "Default")
      (node (ref "U7") (pin "J6") (pinfunction "RFU_J6") (pintype "passive+no_connect"))
    )
    (net (code "59") (name "unconnected-(U7B-RFU-PadJ7)") (class "Default")
      (node (ref "U7") (pin "J7") (pinfunction "RFU_J7") (pintype "passive+no_connect"))
    )
    (net (code "60") (name "unconnected-(U7B-RFU-PadJ8)") (class "Default")
      (node (ref "U7") (pin "J8") (pinfunction "RFU_J8") (pintype "passive+no_connect"))
    )
    (net (code "61") (name "unconnected-(U7B-RFU-PadJ9)") (class "Default")
      (node (ref "U7") (pin "J9") (pinfunction "RFU_J9") (pintype "passive+no_connect"))
    )
    (net (code "62") (name "unconnected-(U7B-RFU-PadK4)") (class "Default")
      (node (ref "U7") (pin "K4") (pinfunction "RFU_K4") (pintype "passive+no_connect"))
    )
    (net (code "63") (name "unconnected-(U7B-RFU-PadK6)") (class "Default")
      (node (ref "U7") (pin "K6") (pinfunction "RFU_K6") (pintype "passive+no_connect"))
    )
    (net (code "64") (name "unconnected-(U7B-RFU-PadK7)") (class "Default")
      (node (ref "U7") (pin "K7") (pinfunction "RFU_K7") (pintype "passive+no_connect"))
    )
    (net (code "65") (name "unconnected-(U7B-RFU-PadL5)") (class "Default")
      (node (ref "U7") (pin "L5") (pinfunction "RFU_L5") (pintype "passive+no_connect"))
    )
    (net (code "66") (name "unconnected-(U7B-RFU-PadL6)") (class "Default")
      (node (ref "U7") (pin "L6") (pinfunction "RFU_L6") (pintype "passive+no_connect"))
    )
    (net (code "67") (name "unconnected-(U7B-RFU-PadM2)") (class "Default")
      (node (ref "U7") (pin "M2") (pinfunction "RFU_M2") (pintype "passive+no_connect"))
    )
    (net (code "68") (name "unconnected-(U7B-RFU-PadM3)") (class "Default")
      (node (ref "U7") (pin "M3") (pinfunction "RFU_M3") (pintype "passive+no_connect"))
    )
    (net (code "69") (name "unconnected-(U7B-RFU-PadM6)") (class "Default")
      (node (ref "U7") (pin "M6") (pinfunction "RFU_M6") (pintype "passive+no_connect"))
    )
    (net (code "70") (name "unconnected-(U7B-RFU-PadM8)") (class "Default")
      (node (ref "U7") (pin "M8") (pinfunction "RFU_M8") (pintype "passive+no_connect"))
    )
    (net (code "71") (name "unconnected-(U7B-RFU-PadM9)") (class "Default")
      (node (ref "U7") (pin "M9") (pinfunction "RFU_M9") (pintype "passive+no_connect"))
    )
    (net (code "72") (name "unconnected-(U7B-RFU-PadN4)") (class "Default")
      (node (ref "U7") (pin "N4") (pinfunction "RFU_N4") (pintype "passive+no_connect"))
    )
    (net (code "73") (name "unconnected-(U7B-RFU-PadN5)") (class "Default")
      (node (ref "U7") (pin "N5") (pinfunction "RFU_N5") (pintype "passive+no_connect"))
    )
    (net (code "74") (name "unconnected-(U7B-RFU-PadN6)") (class "Default")
      (node (ref "U7") (pin "N6") (pinfunction "RFU_N6") (pintype "passive+no_connect"))
    )
    (net (code "75") (name "unconnected-(U7B-RFU-PadN7)") (class "Default")
      (node (ref "U7") (pin "N7") (pinfunction "RFU_N7") (pintype "passive+no_connect"))
    )
    (net (code "76") (name "unconnected-(U7B-RFU-PadP4)") (class "Default")
      (node (ref "U7") (pin "P4") (pinfunction "RFU_P4") (pintype "passive+no_connect"))
    )
    (net (code "77") (name "unconnected-(U7B-RFU-PadP7)") (class "Default")
      (node (ref "U7") (pin "P7") (pinfunction "RFU_P7") (pintype "passive+no_connect"))
    )
    (net (code "78") (name "unconnected-(U8A-DAT4-PadN8)") (class "Default")
      (node (ref "U8") (pin "N8") (pinfunction "DAT4_N8") (pintype "passive+no_connect"))
    )
    (net (code "79") (name "unconnected-(U8A-DAT5-PadK8)") (class "Default")
      (node (ref "U8") (pin "K8") (pinfunction "DAT5_K8") (pintype "passive+no_connect"))
    )
    (net (code "80") (name "unconnected-(U8A-DAT6-PadN9)") (class "Default")
      (node (ref "U8") (pin "N9") (pinfunction "DAT6_N9") (pintype "passive+no_connect"))
    )
    (net (code "81") (name "unconnected-(U8A-DAT7-PadK9)") (class "Default")
      (node (ref "U8") (pin "K9") (pinfunction "DAT7_K9") (pintype "passive+no_connect"))
    )
    (net (code "82") (name "unconnected-(U8A-DS-PadK5)") (class "Default")
      (node (ref "U8") (pin "K5") (pinfunction "DS_K5") (pintype "passive+no_connect"))
    )
    (net (code "83") (name "unconnected-(U8A-VSF1-PadD2)") (class "Default")
      (node (ref "U8") (pin "D2") (pinfunction "VSF1_D2") (pintype "passive+no_connect"))
    )
    (net (code "84") (name "unconnected-(U8A-VSF2-PadD3)") (class "Default")
      (node (ref "U8") (pin "D3") (pinfunction "VSF2_D3") (pintype "passive+no_connect"))
    )
    (net (code "85") (name "unconnected-(U8A-VSF3-PadD4)") (class "Default")
      (node (ref "U8") (pin "D4") (pinfunction "VSF3_D4") (pintype "passive+no_connect"))
    )
    (net (code "86") (name "unconnected-(U8A-VSF4-PadD5)") (class "Default")
      (node (ref "U8") (pin "D5") (pinfunction "VSF4_D5") (pintype "passive+no_connect"))
    )
    (net (code "87") (name "unconnected-(U8A-VSF5-PadD6)") (class "Default")
      (node (ref "U8") (pin "D6") (pinfunction "VSF5_D6") (pintype "passive+no_connect"))
    )
    (net (code "88") (name "unconnected-(U8A-VSF6-PadD7)") (class "Default")
      (node (ref "U8") (pin "D7") (pinfunction "VSF6_D7") (pintype "passive+no_connect"))
    )
    (net (code "89") (name "unconnected-(U8A-VSF7-PadD8)") (class "Default")
      (node (ref "U8") (pin "D8") (pinfunction "VSF7_D8") (pintype "passive+no_connect"))
    )
    (net (code "90") (name "unconnected-(U8A-VSF8-PadD9)") (class "Default")
      (node (ref "U8") (pin "D9") (pinfunction "VSF8_D9") (pintype "passive+no_connect"))
    )
    (net (code "91") (name "unconnected-(U8B-NC-PadA1)") (class "Default")
      (node (ref "U8") (pin "A1") (pinfunction "NC_A1") (pintype "passive+no_connect"))
    )
    (net (code "92") (name "unconnected-(U8B-NC-PadA2)") (class "Default")
      (node (ref "U8") (pin "A2") (pinfunction "NC_A2") (pintype "passive+no_connect"))
    )
    (net (code "93") (name "unconnected-(U8B-NC-PadA9)") (class "Default")
      (node (ref "U8") (pin "A9") (pinfunction "NC_A9") (pintype "passive+no_connect"))
    )
    (net (code "94") (name "unconnected-(U8B-NC-PadA10)") (class "Default")
      (node (ref "U8") (pin "A10") (pinfunction "NC_A10") (pintype "passive+no_connect"))
    )
    (net (code "95") (name "unconnected-(U8B-NC-PadB1)") (class "Default")
      (node (ref "U8") (pin "B1") (pinfunction "NC_B1") (pintype "passive+no_connect"))
    )
    (net (code "96") (name "unconnected-(U8B-NC-PadB10)") (class "Default")
      (node (ref "U8") (pin "B10") (pinfunction "NC_B10") (pintype "passive+no_connect"))
    )
    (net (code "97") (name "unconnected-(U8B-NC-PadT1)") (class "Default")
      (node (ref "U8") (pin "T1") (pinfunction "NC_T1") (pintype "passive+no_connect"))
    )
    (net (code "98") (name "unconnected-(U8B-NC-PadT10)") (class "Default")
      (node (ref "U8") (pin "T10") (pinfunction "NC_T10") (pintype "passive+no_connect"))
    )
    (net (code "99") (name "unconnected-(U8B-NC-PadU1)") (class "Default")
      (node (ref "U8") (pin "U1") (pinfunction "NC_U1") (pintype "passive+no_connect"))
    )
    (net (code "100") (name "unconnected-(U8B-NC-PadU2)") (class "Default")
      (node (ref "U8") (pin "U2") (pinfunction "NC_U2") (pintype "passive+no_connect"))
    )
    (net (code "101") (name "unconnected-(U8B-NC-PadU9)") (class "Default")
      (node (ref "U8") (pin "U9") (pinfunction "NC_U9") (pintype "passive+no_connect"))
    )
    (net (code "102") (name "unconnected-(U8B-NC-PadU10)") (class "Default")
      (node (ref "U8") (pin "U10") (pinfunction "NC_U10") (pintype "passive+no_connect"))
    )
    (net (code "103") (name "unconnected-(U8B-RFU-PadE2)") (class "Default")
      (node (ref "U8") (pin "E2") (pinfunction "RFU_E2") (pintype "passive+no_connect"))
    )
    (net (code "104") (name "unconnected-(U8B-RFU-PadE3)") (class "Default")
      (node (ref "U8") (pin "E3") (pinfunction "RFU_E3") (pintype "passive+no_connect"))
    )
    (net (code "105") (name "unconnected-(U8B-RFU-PadE5)") (class "Default")
      (node (ref "U8") (pin "E5") (pinfunction "RFU_E5") (pintype "passive+no_connect"))
    )
    (net (code "106") (name "unconnected-(U8B-RFU-PadE6)") (class "Default")
      (node (ref "U8") (pin "E6") (pinfunction "RFU_E6") (pintype "passive+no_connect"))
    )
    (net (code "107") (name "unconnected-(U8B-RFU-PadE7)") (class "Default")
      (node (ref "U8") (pin "E7") (pinfunction "RFU_E7") (pintype "passive+no_connect"))
    )
    (net (code "108") (name "unconnected-(U8B-RFU-PadE8)") (class "Default")
      (node (ref "U8") (pin "E8") (pinfunction "RFU_E8") (pintype "passive+no_connect"))
    )
    (net (code "109") (name "unconnected-(U8B-RFU-PadE9)") (class "Default")
      (node (ref "U8") (pin "E9") (pinfunction "RFU_E9") (pintype "passive+no_connect"))
    )
    (net (code "110") (name "unconnected-(U8B-RFU-PadH4)") (class "Default")
      (node (ref "U8") (pin "H4") (pinfunction "RFU_H4") (pintype "passive+no_connect"))
    )
    (net (code "111") (name "unconnected-(U8B-RFU-PadH5)") (class "Default")
      (node (ref "U8") (pin "H5") (pinfunction "RFU_H5") (pintype "passive+no_connect"))
    )
    (net (code "112") (name "unconnected-(U8B-RFU-PadH6)") (class "Default")
      (node (ref "U8") (pin "H6") (pinfunction "RFU_H6") (pintype "passive+no_connect"))
    )
    (net (code "113") (name "unconnected-(U8B-RFU-PadH7)") (class "Default")
      (node (ref "U8") (pin "H7") (pinfunction "RFU_H7") (pintype "passive+no_connect"))
    )
    (net (code "114") (name "unconnected-(U8B-RFU-PadJ2)") (class "Default")
      (node (ref "U8") (pin "J2") (pinfunction "RFU_J2") (pintype "passive+no_connect"))
    )
    (net (code "115") (name "unconnected-(U8B-RFU-PadJ3)") (class "Default")
      (node (ref "U8") (pin "J3") (pinfunction "RFU_J3") (pintype "passive+no_connect"))
    )
    (net (code "116") (name "unconnected-(U8B-RFU-PadJ4)") (class "Default")
      (node (ref "U8") (pin "J4") (pinfunction "RFU_J4") (pintype "passive+no_connect"))
    )
    (net (code "117") (name "unconnected-(U8B-RFU-PadJ6)") (class "Default")
      (node (ref "U8") (pin "J6") (pinfunction "RFU_J6") (pintype "passive+no_connect"))
    )
    (net (code "118") (name "unconnected-(U8B-RFU-PadJ7)") (class "Default")
      (node (ref "U8") (pin "J7") (pinfunction "RFU_J7") (pintype "passive+no_connect"))
    )
    (net (code "119") (name "unconnected-(U8B-RFU-PadJ8)") (class "Default")
      (node (ref "U8") (pin "J8") (pinfunction "RFU_J8") (pintype "passive+no_connect"))
    )
    (net (code "120") (name "unconnected-(U8B-RFU-PadJ9)") (class "Default")
      (node (ref "U8") (pin "J9") (pinfunction "RFU_J9") (pintype "passive+no_connect"))
    )
    (net (code "121") (name "unconnected-(U8B-RFU-PadK4)") (class "Default")
      (node (ref "U8") (pin "K4") (pinfunction "RFU_K4") (pintype "passive+no_connect"))
    )
    (net (code "122") (name "unconnected-(U8B-RFU-PadK6)") (class "Default")
      (node (ref "U8") (pin "K6") (pinfunction "RFU_K6") (pintype "passive+no_connect"))
    )
    (net (code "123") (name "unconnected-(U8B-RFU-PadK7)") (class "Default")
      (node (ref "U8") (pin "K7") (pinfunction "RFU_K7") (pintype "passive+no_connect"))
    )
    (net (code "124") (name "unconnected-(U8B-RFU-PadL5)") (class "Default")
      (node (ref "U8") (pin "L5") (pinfunction "RFU_L5") (pintype "passive+no_connect"))
    )
    (net (code "125") (name "unconnected-(U8B-RFU-PadL6)") (class "Default")
      (node (ref "U8") (pin "L6") (pinfunction "RFU_L6") (pintype "passive+no_connect"))
    )
    (net (code "126") (name "unconnected-(U8B-RFU-PadM2)") (class "Default")
      (node (ref "U8") (pin "M2") (pinfunction "RFU_M2") (pintype "passive+no_connect"))
    )
    (net (code "127") (name "unconnected-(U8B-RFU-PadM3)") (class "Default")
      (node (ref "U8") (pin "M3") (pinfunction "RFU_M3") (pintype "passive+no_connect"))
    )
    (net (code "128") (name "unconnected-(U8B-RFU-PadM6)") (class "Default")
      (node (ref "U8") (pin "M6") (pinfunction "RFU_M6") (pintype "passive+no_connect"))
    )
    (net (code "129") (name "unconnected-(U8B-RFU-PadM8)") (class "Default")
      (node (ref "U8") (pin "M8") (pinfunction "RFU_M8") (pintype "passive+no_connect"))
    )
    (net (code "130") (name "unconnected-(U8B-RFU-PadM9)") (class "Default")
      (node (ref "U8") (pin "M9") (pinfunction "RFU_M9") (pintype "passive+no_connect"))
    )
    (net (code "131") (name "unconnected-(U8B-RFU-PadN4)") (class "Default")
      (node (ref "U8") (pin "N4") (pinfunction "RFU_N4") (pintype "passive+no_connect"))
    )
    (net (code "132") (name "unconnected-(U8B-RFU-PadN5)") (class "Default")
      (node (ref "U8") (pin "N5") (pinfunction "RFU_N5") (pintype "passive+no_connect"))
    )
    (net (code "133") (name "unconnected-(U8B-RFU-PadN6)") (class "Default")
      (node (ref "U8") (pin "N6") (pinfunction "RFU_N6") (pintype "passive+no_connect"))
    )
    (net (code "134") (name "unconnected-(U8B-RFU-PadN7)") (class "Default")
      (node (ref "U8") (pin "N7") (pinfunction "RFU_N7") (pintype "passive+no_connect"))
    )
    (net (code "135") (name "unconnected-(U8B-RFU-PadP4)") (class "Default")
      (node (ref "U8") (pin "P4") (pinfunction "RFU_P4") (pintype "passive+no_connect"))
    )
    (net (code "136") (name "unconnected-(U8B-RFU-PadP7)") (class "Default")
      (node (ref "U8") (pin "P7") (pinfunction "RFU_P7") (pintype "passive+no_connect"))
    )
  )
)
